# Sensors.net
KiCad netlist of a schematic drawn in Altium Designer
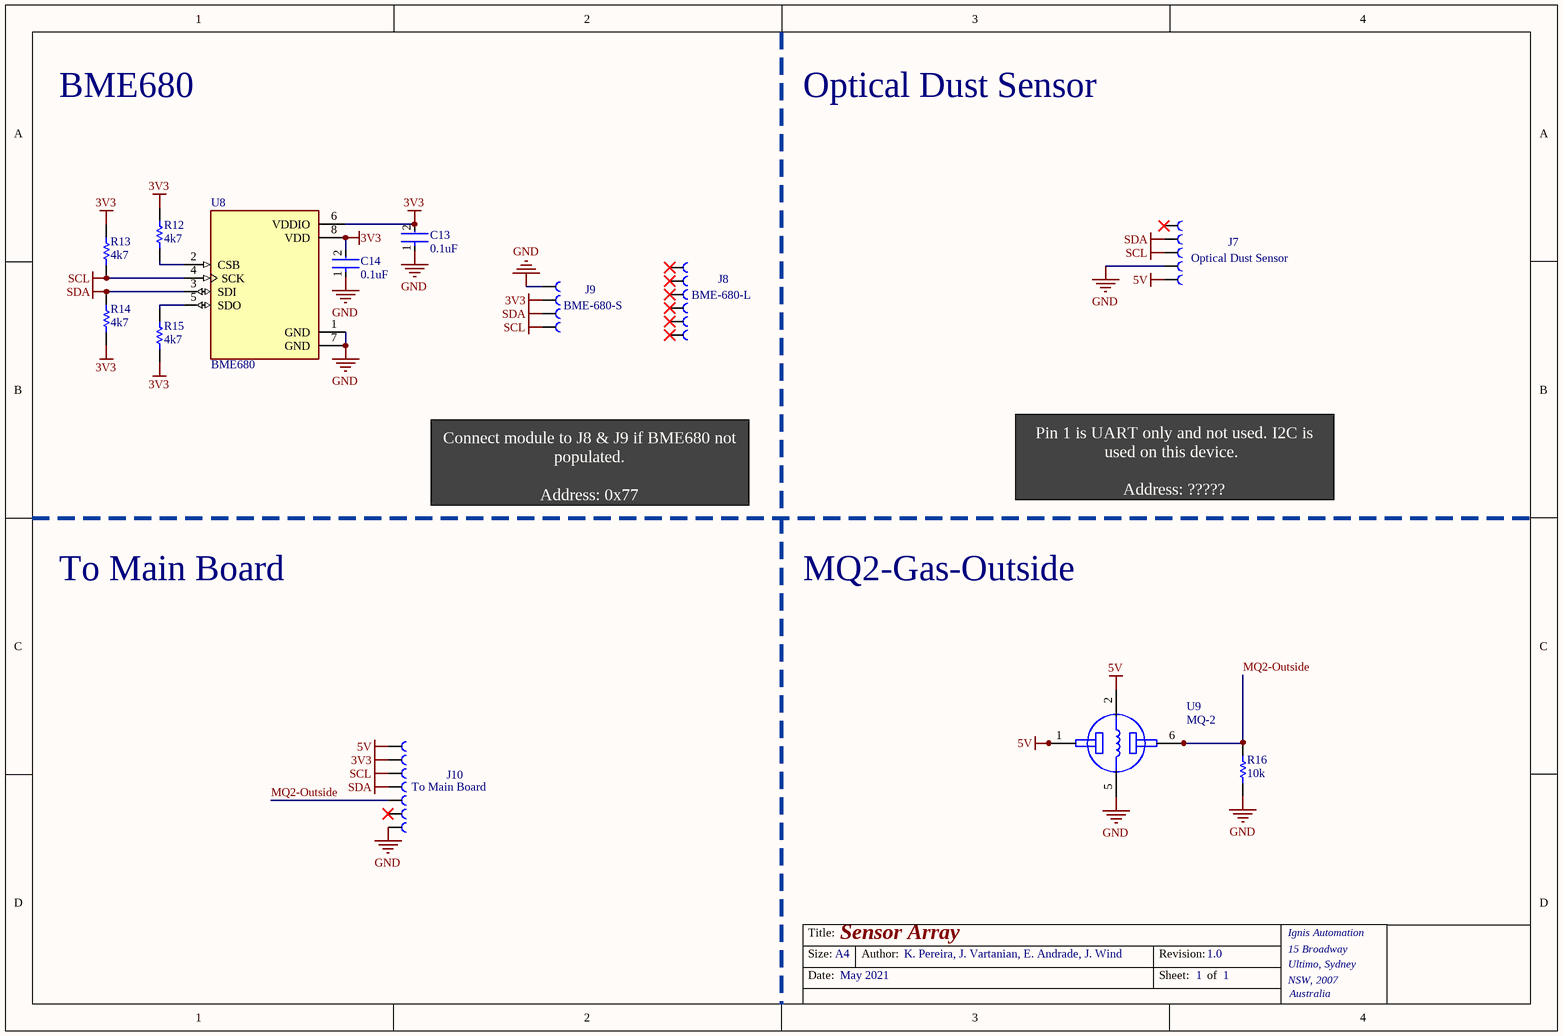
[diagram p0: Sensors.SchDoc]

(export (version "E")
  (design (tool "Eeschema 10.0.6"))
  (components
    (comp (ref "C13")
      (value "0.1uF")
      (footprint "FP-CL10-IPC_C")
      (description "CAP CER 0.1UF 50V X7R 0603")
      (fields (field (name "PART NUMBER") "1276-CL10B104KB8NNNLCT-NDT-ND"))
      (libsource (lib "Altium Content Vault") (part "b4654b650e69147ec39a6b967a45e02"))
    )
    (comp (ref "C14")
      (value "0.1uF")
      (footprint "FP-CL10-IPC_C")
      (description "CAP CER 0.1UF 50V X7R 0603")
      (fields (field (name "PART NUMBER") "1276-CL10B104KB8NNNLCT-ND"))
      (libsource (lib "Altium Content Vault") (part "b4654b650e69147ec39a6b967a45e02"))
    )
    (comp (ref "J7")
      (value "Optical Dust Sensor")
      (footprint "5pin:61300711821")
      (description "5 Pin")
      (libsource (lib "5pin") (part "61300711821"))
    )
    (comp (ref "J8")
      (value "BME-680-L")
      (footprint "6pin:61300711821")
      (description "6 Pin")
      (libsource (lib "6pin") (part "61300711821"))
    )
    (comp (ref "J9")
      (value "BME-680-S")
      (footprint "4pin:61300711821")
      (description "4 Pin")
      (libsource (lib "4pin") (part "61300711821"))
    )
    (comp (ref "J10")
      (value "To Main Board")
      (footprint "7pin:61300711821")
      (description "7 Pin")
      (libsource (lib "7pin") (part "61300711821"))
    )
    (comp (ref "R12")
      (value "4k7")
      (footprint "RESC1608X55X30NL15T15")
      (description "RES SMD 4.7K OHM 1% 1/10W 0603")
      (fields (field (name "PART NUMBER") "311-4.70KHRCT-ND"))
      (libsource (lib "Altium Content Vault") (part "RES"))
    )
    (comp (ref "R13")
      (value "4k7")
      (footprint "RESC1608X55X30NL15T15")
      (description "RES SMD 4.7K OHM 1% 1/10W 0603")
      (fields (field (name "PART NUMBER") "311-4.70KHRCT-ND"))
      (libsource (lib "Altium Content Vault") (part "RES"))
    )
    (comp (ref "R14")
      (value "4k7")
      (footprint "RESC1608X55X30NL15T15")
      (description "RES SMD 4.7K OHM 1% 1/10W 0603")
      (fields (field (name "PART NUMBER") "311-4.70KHRCT-ND"))
      (libsource (lib "Altium Content Vault") (part "RES"))
    )
    (comp (ref "R15")
      (value "4k7")
      (footprint "RESC1608X55X30NL15T15")
      (description "RES SMD 4.7K OHM 1% 1/10W 0603")
      (fields (field (name "PART NUMBER") "311-4.70KHRCT-ND"))
      (libsource (lib "Altium Content Vault") (part "RES"))
    )
    (comp (ref "R16")
      (value "10k")
      (footprint "RESC1608X55X30NL15T15")
      (description "RES SMD 10K OHM 1% 1/10W 0603")
      (fields (field (name "PART NUMBER") "A121523CT-ND"))
      (libsource (lib "Altium Content Vault") (part "RES"))
    )
    (comp (ref "U8")
      (value "BME680")
      (footprint "BME680:PSON80P300X300X100-8N")
      (description "SENSOR RH PRESSURE TEMP VOC")
      (fields (field (name "PART NUMBER") "828-1077-1-ND"))
      (libsource (lib "BME680") (part "BME680"))
    )
    (comp (ref "U9")
      (value "MQ-2")
      (footprint "MQ-2:XDCR_SEN-08880")
      (description "MQ-2 Gas Sensor")
      (libsource (lib "MQ-2") (part "MQ-2"))
    )
  )
  (nets
    (net (code "1") (name "/MQ2-Outside") (class "Default")
      (node (ref "J10") (pin "5") (pinfunction "5_5") (pintype "passive"))
      (node (ref "R16") (pin "2") (pinfunction "2_2") (pintype "passive"))
      (node (ref "U9") (pin "4") (pinfunction "B_4") (pintype "passive"))
      (node (ref "U9") (pin "6") (pinfunction "B_6") (pintype "passive"))
    )
    (net (code "2") (name "3V3") (class "Default")
      (node (ref "C13") (pin "2") (pinfunction "2_2") (pintype "passive"))
      (node (ref "C14") (pin "2") (pinfunction "2_2") (pintype "passive"))
      (node (ref "J10") (pin "2") (pinfunction "2_2") (pintype "passive"))
      (node (ref "J9") (pin "2") (pinfunction "2_2") (pintype "passive"))
      (node (ref "R12") (pin "2") (pinfunction "2_2") (pintype "passive"))
      (node (ref "R13") (pin "2") (pinfunction "2_2") (pintype "passive"))
      (node (ref "R14") (pin "1") (pinfunction "1_1") (pintype "passive"))
      (node (ref "R15") (pin "1") (pinfunction "1_1") (pintype "passive"))
      (node (ref "U8") (pin "6") (pinfunction "VDDIO_6") (pintype "power_in"))
      (node (ref "U8") (pin "8") (pinfunction "VDD_8") (pintype "power_in"))
    )
    (net (code "3") (name "5V") (class "Default")
      (node (ref "J10") (pin "1") (pinfunction "1_1") (pintype "passive"))
      (node (ref "J7") (pin "5") (pinfunction "5_5") (pintype "passive"))
      (node (ref "U9") (pin "1") (pinfunction "A_1") (pintype "passive"))
      (node (ref "U9") (pin "2") (pinfunction "H1_2") (pintype "passive"))
      (node (ref "U9") (pin "3") (pinfunction "A_3") (pintype "passive"))
    )
    (net (code "4") (name "GND") (class "Default")
      (node (ref "C13") (pin "1") (pinfunction "1_1") (pintype "passive"))
      (node (ref "C14") (pin "1") (pinfunction "1_1") (pintype "passive"))
      (node (ref "J10") (pin "7") (pinfunction "7_7") (pintype "passive"))
      (node (ref "J7") (pin "4") (pinfunction "4_4") (pintype "passive"))
      (node (ref "J9") (pin "1") (pinfunction "1_1") (pintype "passive"))
      (node (ref "R16") (pin "1") (pinfunction "1_1") (pintype "passive"))
      (node (ref "U8") (pin "1") (pinfunction "GND_1") (pintype "power_in"))
      (node (ref "U8") (pin "7") (pinfunction "GND_7") (pintype "power_in"))
      (node (ref "U9") (pin "5") (pinfunction "H2_5") (pintype "passive"))
    )
    (net (code "5") (name "Net-(U8-CSB)") (class "Default")
      (node (ref "R12") (pin "1") (pinfunction "1_1") (pintype "passive"))
      (node (ref "U8") (pin "2") (pinfunction "CSB_2") (pintype "input"))
    )
    (net (code "6") (name "Net-(U8-SDO)") (class "Default")
      (node (ref "R15") (pin "2") (pinfunction "2_2") (pintype "passive"))
      (node (ref "U8") (pin "5") (pinfunction "SDO_5") (pintype "bidirectional"))
    )
    (net (code "7") (name "SCL") (class "Default")
      (node (ref "J10") (pin "3") (pinfunction "3_3") (pintype "passive"))
      (node (ref "J7") (pin "3") (pinfunction "3_3") (pintype "passive"))
      (node (ref "J9") (pin "4") (pinfunction "4_4") (pintype "passive"))
      (node (ref "R13") (pin "1") (pinfunction "1_1") (pintype "passive"))
      (node (ref "U8") (pin "4") (pinfunction "SCK_4") (pintype "input"))
    )
    (net (code "8") (name "SDA") (class "Default")
      (node (ref "J10") (pin "4") (pinfunction "4_4") (pintype "passive"))
      (node (ref "J7") (pin "2") (pinfunction "2_2") (pintype "passive"))
      (node (ref "J9") (pin "3") (pinfunction "3_3") (pintype "passive"))
      (node (ref "R14") (pin "2") (pinfunction "2_2") (pintype "passive"))
      (node (ref "U8") (pin "3") (pinfunction "SDI_3") (pintype "bidirectional"))
    )
    (net (code "9") (name "unconnected-(J7-Pad1)") (class "Default")
      (node (ref "J7") (pin "1") (pinfunction "1_1") (pintype "passive+no_connect"))
    )
    (net (code "10") (name "unconnected-(J8-Pad1)") (class "Default")
      (node (ref "J8") (pin "1") (pinfunction "1_1") (pintype "passive+no_connect"))
    )
    (net (code "11") (name "unconnected-(J8-Pad2)") (class "Default")
      (node (ref "J8") (pin "2") (pinfunction "2_2") (pintype "passive+no_connect"))
    )
    (net (code "12") (name "unconnected-(J8-Pad3)") (class "Default")
      (node (ref "J8") (pin "3") (pinfunction "3_3") (pintype "passive+no_connect"))
    )
    (net (code "13") (name "unconnected-(J8-Pad4)") (class "Default")
      (node (ref "J8") (pin "4") (pinfunction "4_4") (pintype "passive+no_connect"))
    )
    (net (code "14") (name "unconnected-(J8-Pad5)") (class "Default")
      (node (ref "J8") (pin "5") (pinfunction "5_5") (pintype "passive+no_connect"))
    )
    (net (code "15") (name "unconnected-(J8-Pad6)") (class "Default")
      (node (ref "J8") (pin "6") (pinfunction "6_6") (pintype "passive+no_connect"))
    )
    (net (code "16") (name "unconnected-(J10-Pad6)") (class "Default")
      (node (ref "J10") (pin "6") (pinfunction "6_6") (pintype "passive+no_connect"))
    )
  )
)
